# v1.net
KiCad netlist of a schematic drawn in EAGLE
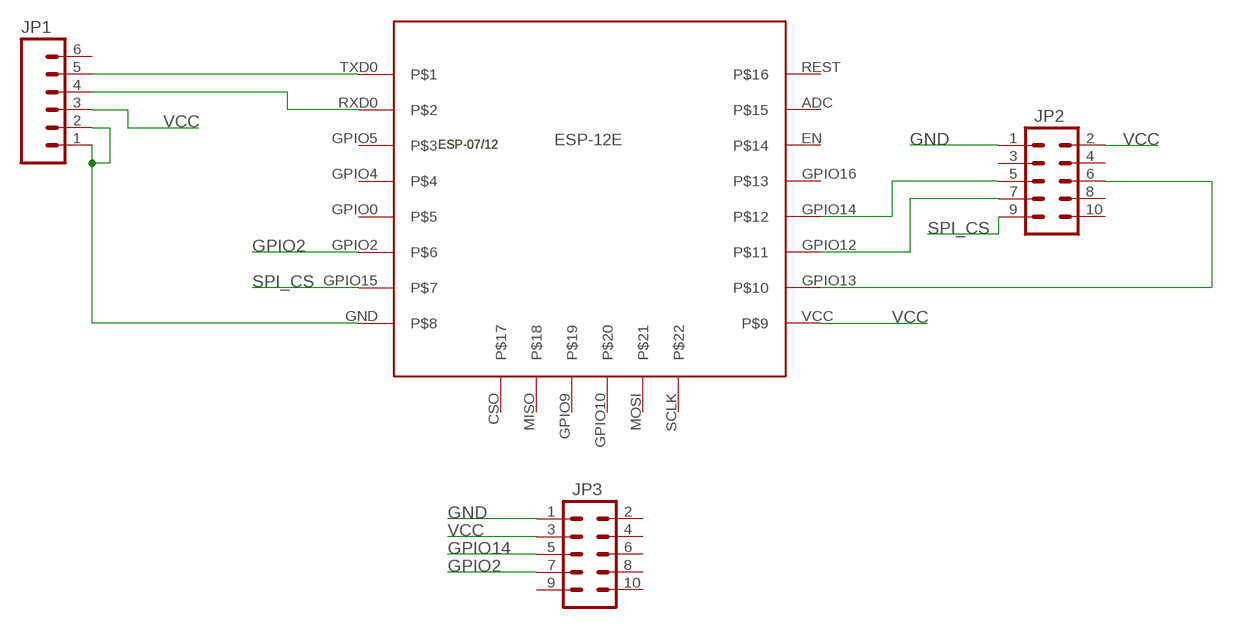
[diagram p0: schematic, sheet 1]

(export (version "E")
  (design (tool "Eeschema 10.0.6"))
  (components
    (comp (ref "JP1")
      (value "M06SILK_FEMALE_PTH")
      (footprint "eagle-import:1X06")
      (libsource (lib "eagle-import") (part "M06SILK_FEMALE_PTH"))
    )
    (comp (ref "JP2")
      (value "M05X2PTH")
      (footprint "eagle-import:AVR_ICSP")
      (libsource (lib "eagle-import") (part "M05X2PTH"))
    )
    (comp (ref "JP3")
      (value "M05X2PTH")
      (footprint "eagle-import:AVR_ICSP")
      (libsource (lib "eagle-import") (part "M05X2PTH"))
    )
    (comp (ref "U$1")
      (value "ESP-07/12_ESP-12E")
      (footprint "eagle-import:ESP-07_12")
      (libsource (lib "eagle-import") (part "ESP-07/12_ESP-12E"))
    )
  )
  (nets
    (net (code "1") (name "/GND") (class "Default")
      (node (ref "JP2") (pin "1") (pinfunction "1_1") (pintype "passive"))
      (node (ref "JP3") (pin "1") (pinfunction "1_1") (pintype "passive"))
    )
    (net (code "2") (name "/GPIO2") (class "Default")
      (node (ref "JP3") (pin "7") (pinfunction "7_7") (pintype "passive"))
      (node (ref "U$1") (pin "GPIO2") (pinfunction "P$6_GPIO2") (pintype "bidirectional"))
    )
    (net (code "3") (name "/GPIO14") (class "Default")
      (node (ref "JP2") (pin "5") (pinfunction "5_5") (pintype "passive"))
      (node (ref "JP3") (pin "5") (pinfunction "5_5") (pintype "passive"))
      (node (ref "U$1") (pin "GPIO14") (pinfunction "P$12_GPIO14") (pintype "bidirectional"))
    )
    (net (code "4") (name "/SPI_CS") (class "Default")
      (node (ref "JP2") (pin "9") (pinfunction "9_9") (pintype "passive"))
      (node (ref "U$1") (pin "GPIO15") (pinfunction "P$7_GPIO15") (pintype "bidirectional"))
    )
    (net (code "5") (name "/VCC") (class "Default")
      (node (ref "JP1") (pin "3") (pinfunction "3_3") (pintype "passive"))
      (node (ref "JP2") (pin "2") (pinfunction "2_2") (pintype "passive"))
      (node (ref "JP3") (pin "3") (pinfunction "3_3") (pintype "passive"))
      (node (ref "U$1") (pin "VCC") (pinfunction "P$9_VCC") (pintype "bidirectional"))
    )
    (net (code "6") (name "Net-(U$1-P$1)") (class "Default")
      (node (ref "JP1") (pin "5") (pinfunction "5_5") (pintype "passive"))
      (node (ref "U$1") (pin "TXD0") (pinfunction "P$1_TXD0") (pintype "bidirectional"))
    )
    (net (code "7") (name "Net-(U$1-P$2)") (class "Default")
      (node (ref "JP1") (pin "4") (pinfunction "4_4") (pintype "passive"))
      (node (ref "U$1") (pin "RXD0") (pinfunction "P$2_RXD0") (pintype "bidirectional"))
    )
    (net (code "8") (name "Net-(U$1-P$8)") (class "Default")
      (node (ref "JP1") (pin "1") (pinfunction "1_1") (pintype "passive"))
      (node (ref "JP1") (pin "2") (pinfunction "2_2") (pintype "passive"))
      (node (ref "U$1") (pin "GND") (pinfunction "P$8_GND") (pintype "bidirectional"))
    )
    (net (code "9") (name "Net-(U$1-P$10)") (class "Default")
      (node (ref "JP2") (pin "6") (pinfunction "6_6") (pintype "passive"))
      (node (ref "U$1") (pin "GPIO13") (pinfunction "P$10_GPIO13") (pintype "bidirectional"))
    )
    (net (code "10") (name "Net-(U$1-P$11)") (class "Default")
      (node (ref "JP2") (pin "7") (pinfunction "7_7") (pintype "passive"))
      (node (ref "U$1") (pin "GPIO12") (pinfunction "P$11_GPIO12") (pintype "bidirectional"))
    )
    (net (code "11") (name "unconnected-(JP1-Pad6)") (class "Default")
      (node (ref "JP1") (pin "6") (pinfunction "6_6") (pintype "passive"))
    )
    (net (code "12") (name "unconnected-(JP2-Pad3)") (class "Default")
      (node (ref "JP2") (pin "3") (pinfunction "3_3") (pintype "passive"))
    )
    (net (code "13") (name "unconnected-(JP2-Pad4)") (class "Default")
      (node (ref "JP2") (pin "4") (pinfunction "4_4") (pintype "passive"))
    )
    (net (code "14") (name "unconnected-(JP2-Pad8)") (class "Default")
      (node (ref "JP2") (pin "8") (pinfunction "8_8") (pintype "passive"))
    )
    (net (code "15") (name "unconnected-(JP2-Pad10)") (class "Default")
      (node (ref "JP2") (pin "10") (pinfunction "10_10") (pintype "passive"))
    )
    (net (code "16") (name "unconnected-(JP3-Pad2)") (class "Default")
      (node (ref "JP3") (pin "2") (pinfunction "2_2") (pintype "passive"))
    )
    (net (code "17") (name "unconnected-(JP3-Pad4)") (class "Default")
      (node (ref "JP3") (pin "4") (pinfunction "4_4") (pintype "passive"))
    )
    (net (code "18") (name "unconnected-(JP3-Pad6)") (class "Default")
      (node (ref "JP3") (pin "6") (pinfunction "6_6") (pintype "passive"))
    )
    (net (code "19") (name "unconnected-(JP3-Pad8)") (class "Default")
      (node (ref "JP3") (pin "8") (pinfunction "8_8") (pintype "passive"))
    )
    (net (code "20") (name "unconnected-(JP3-Pad9)") (class "Default")
      (node (ref "JP3") (pin "9") (pinfunction "9_9") (pintype "passive"))
    )
    (net (code "21") (name "unconnected-(JP3-Pad10)") (class "Default")
      (node (ref "JP3") (pin "10") (pinfunction "10_10") (pintype "passive"))
    )
    (net (code "22") (name "unconnected-(U$1-P$3-PadGPIO5)") (class "Default")
      (node (ref "U$1") (pin "GPIO5") (pinfunction "P$3_GPIO5") (pintype "bidirectional"))
    )
    (net (code "23") (name "unconnected-(U$1-P$4-PadGPIO4)") (class "Default")
      (node (ref "U$1") (pin "GPIO4") (pinfunction "P$4_GPIO4") (pintype "bidirectional"))
    )
    (net (code "24") (name "unconnected-(U$1-P$5-PadGPIO0)") (class "Default")
      (node (ref "U$1") (pin "GPIO0") (pinfunction "P$5_GPIO0") (pintype "bidirectional"))
    )
    (net (code "25") (name "unconnected-(U$1-P$13-PadGPIO16)") (class "Default")
      (node (ref "U$1") (pin "GPIO16") (pinfunction "P$13_GPIO16") (pintype "bidirectional"))
    )
    (net (code "26") (name "unconnected-(U$1-P$14-PadEN)") (class "Default")
      (node (ref "U$1") (pin "EN") (pinfunction "P$14_EN") (pintype "bidirectional"))
    )
    (net (code "27") (name "unconnected-(U$1-P$15-PadADC)") (class "Default")
      (node (ref "U$1") (pin "ADC") (pinfunction "P$15_ADC") (pintype "bidirectional"))
    )
    (net (code "28") (name "unconnected-(U$1-P$16-PadREST)") (class "Default")
      (node (ref "U$1") (pin "REST") (pinfunction "P$16_REST") (pintype "bidirectional"))
    )
    (net (code "29") (name "unconnected-(U$1-P$17-PadCSO)") (class "Default")
      (node (ref "U$1") (pin "CSO") (pinfunction "P$17_CSO") (pintype "bidirectional"))
    )
    (net (code "30") (name "unconnected-(U$1-P$18-PadMISO)") (class "Default")
      (node (ref "U$1") (pin "MISO") (pinfunction "P$18_MISO") (pintype "bidirectional"))
    )
    (net (code "31") (name "unconnected-(U$1-P$19-PadGPIO9)") (class "Default")
      (node (ref "U$1") (pin "GPIO9") (pinfunction "P$19_GPIO9") (pintype "bidirectional"))
    )
    (net (code "32") (name "unconnected-(U$1-P$20-PadGPIO10)") (class "Default")
      (node (ref "U$1") (pin "GPIO10") (pinfunction "P$20_GPIO10") (pintype "bidirectional"))
    )
    (net (code "33") (name "unconnected-(U$1-P$21-PadMOSI)") (class "Default")
      (node (ref "U$1") (pin "MOSI") (pinfunction "P$21_MOSI") (pintype "bidirectional"))
    )
    (net (code "34") (name "unconnected-(U$1-P$22-PadSCLK)") (class "Default")
      (node (ref "U$1") (pin "SCLK") (pinfunction "P$22_SCLK") (pintype "bidirectional"))
    )
  )
)
